# karmanDB_amp.net
KiCad netlist of a schematic drawn in Altium Designer
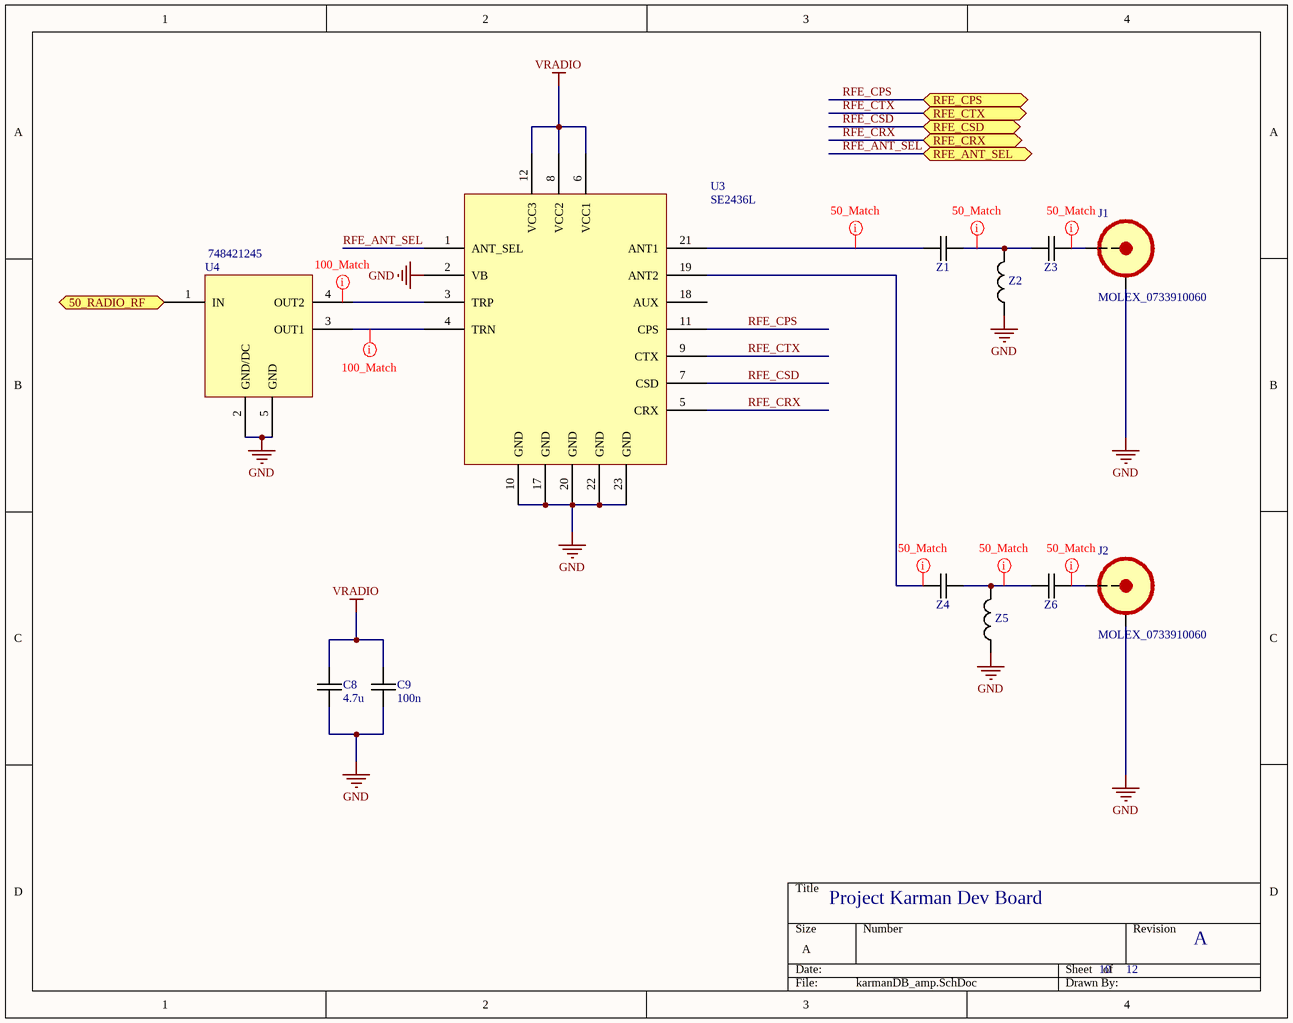
[diagram p0: karmanDB_amp.SchDoc]

(export (version "E")
  (design (tool "Eeschema 10.0.6"))
  (components
    (comp (ref "C8")
      (value "4.7u")
      (footprint "MURATA_GRM_0603")
      (description "CAP CER 4.7UF 16V 20% X5R 0603")
      (fields
        (field (name "MANUFACTURER") "Murata Electronics North America")
        (field (name "MANUFACTURER PART NUMBER") "GRM188R61C475MAAJD")
      )
      (libsource (lib "project_symbols") (part "CAP_MURATA_GRM188R61C475MAAJD"))
    )
    (comp (ref "C9")
      (value "100n")
      (footprint "MURATA_GRM_0603")
      (description "CAP CER 0.1UF 16V 10% X7R 0603")
      (fields
        (field (name "MANUFACTURER") "Murata Electronics North America")
        (field (name "MANUFACTURER PART NUMBER") "GRM188R71C104KA01D")
      )
      (libsource (lib "project_symbols") (part "CAP_MURATA_GRM188R71C104KA01D"))
    )
    (comp (ref "J1")
      (value "MOLEX_0733910060")
      (footprint "MOLEX_0733910060")
      (description "CONN SMA JACK STR 50 OHM PCB")
      (fields
        (field (name "MANUFACTURER") "Molex Inc")
        (field (name "MANUFACTURER PART NUMBER") "0733910060")
      )
      (libsource (lib "project_symbols") (part "MOLEX_0733910060"))
    )
    (comp (ref "J2")
      (value "MOLEX_0733910060")
      (footprint "MOLEX_0733910060")
      (description "CONN SMA JACK STR 50 OHM PCB")
      (fields
        (field (name "MANUFACTURER") "Molex Inc")
        (field (name "MANUFACTURER PART NUMBER") "0733910060")
      )
      (libsource (lib "project_symbols") (part "MOLEX_0733910060"))
    )
    (comp (ref "U3")
      (value "SE2436L")
      (footprint "9 SE2436L")
      (description "ZIGBEE FRONT END MODULE")
      (fields (field (name "MANUFACTURER") "Skyworks Solutions Inc."))
      (libsource (lib "karman_pcb") (part "SE2436L"))
    )
    (comp (ref "U4")
      (value "748421245")
      (footprint "748421245")
      (description "BALUN EMBER351 & 357 0805 SMD")
      (fields (field (name "MANUFACTURER") "Wurth Electronics Inc"))
      (libsource (lib "karman_pcb") (part "748421245"))
    )
    (comp (ref "Z1")
      (value "CAP_GENERIC_0402")
      (footprint "MURATA_GRM_0402")
      (description "Generic Capacitor 0402 Package")
      (libsource (lib "project_symbols") (part "CAP_GENERIC_0402"))
    )
    (comp (ref "Z2")
      (value "IND_GENERIC_0402")
      (footprint "PANASONIC_ELJRF")
      (description "Generic Inductor 0402 Package")
      (libsource (lib "project_symbols") (part "IND_GENERIC_0402"))
    )
    (comp (ref "Z3")
      (value "CAP_GENERIC_0402")
      (footprint "MURATA_GRM_0402")
      (description "Generic Capacitor 0402 Package")
      (libsource (lib "project_symbols") (part "CAP_GENERIC_0402"))
    )
    (comp (ref "Z4")
      (value "CAP_GENERIC_0402")
      (footprint "MURATA_GRM_0402")
      (description "Generic Capacitor 0402 Package")
      (libsource (lib "project_symbols") (part "CAP_GENERIC_0402"))
    )
    (comp (ref "Z5")
      (value "IND_GENERIC_0402")
      (footprint "PANASONIC_ELJRF")
      (description "Generic Inductor 0402 Package")
      (libsource (lib "project_symbols") (part "IND_GENERIC_0402"))
    )
    (comp (ref "Z6")
      (value "CAP_GENERIC_0402")
      (footprint "MURATA_GRM_0402")
      (description "Generic Capacitor 0402 Package")
      (libsource (lib "project_symbols") (part "CAP_GENERIC_0402"))
    )
  )
  (nets
    (net (code "1") (name "/50_RADIO_RF") (class "Default")
      (node (ref "U4") (pin "1") (pinfunction "IN_1") (pintype "passive"))
    )
    (net (code "2") (name "/RFE_ANT_SEL") (class "Default")
      (node (ref "U3") (pin "1") (pinfunction "ANT_SEL_1") (pintype "passive"))
    )
    (net (code "3") (name "/RFE_CPS") (class "Default")
      (node (ref "U3") (pin "11") (pinfunction "CPS_11") (pintype "passive"))
    )
    (net (code "4") (name "/RFE_CRX") (class "Default")
      (node (ref "U3") (pin "5") (pinfunction "CRX_5") (pintype "passive"))
    )
    (net (code "5") (name "/RFE_CSD") (class "Default")
      (node (ref "U3") (pin "7") (pinfunction "CSD_7") (pintype "passive"))
    )
    (net (code "6") (name "/RFE_CTX") (class "Default")
      (node (ref "U3") (pin "9") (pinfunction "CTX_9") (pintype "passive"))
    )
    (net (code "7") (name "GND") (class "Default")
      (node (ref "C8") (pin "2") (pintype "passive"))
      (node (ref "C9") (pin "2") (pintype "passive"))
      (node (ref "J1") (pin "SHIELD") (pintype "passive"))
      (node (ref "J2") (pin "SHIELD") (pintype "passive"))
      (node (ref "U3") (pin "10") (pinfunction "GND_10") (pintype "passive"))
      (node (ref "U3") (pin "17") (pinfunction "GND_17") (pintype "passive"))
      (node (ref "U3") (pin "2") (pinfunction "VB_2") (pintype "passive"))
      (node (ref "U3") (pin "20") (pinfunction "GND_20") (pintype "passive"))
      (node (ref "U3") (pin "22") (pinfunction "GND_22") (pintype "passive"))
      (node (ref "U3") (pin "23") (pinfunction "GND_23") (pintype "passive"))
      (node (ref "U4") (pin "2") (pinfunction "GND/DC_2") (pintype "passive"))
      (node (ref "U4") (pin "5") (pinfunction "GND_5") (pintype "passive"))
      (node (ref "Z2") (pin "1") (pinfunction "1_1") (pintype "passive"))
      (node (ref "Z5") (pin "1") (pinfunction "1_1") (pintype "passive"))
    )
    (net (code "8") (name "Net-(J1-PadPIN)") (class "Default")
      (node (ref "J1") (pin "PIN") (pintype "passive"))
      (node (ref "Z3") (pin "2") (pintype "passive"))
    )
    (net (code "9") (name "Net-(J2-PadPIN)") (class "Default")
      (node (ref "J2") (pin "PIN") (pintype "passive"))
      (node (ref "Z6") (pin "2") (pintype "passive"))
    )
    (net (code "10") (name "Net-(U3-ANT1)") (class "Default")
      (node (ref "U3") (pin "21") (pinfunction "ANT1_21") (pintype "passive"))
      (node (ref "Z1") (pin "1") (pintype "passive"))
    )
    (net (code "11") (name "Net-(U3-ANT2)") (class "Default")
      (node (ref "U3") (pin "19") (pinfunction "ANT2_19") (pintype "passive"))
      (node (ref "Z4") (pin "1") (pintype "passive"))
    )
    (net (code "12") (name "Net-(U3-TRN)") (class "Default")
      (node (ref "U3") (pin "4") (pinfunction "TRN_4") (pintype "passive"))
      (node (ref "U4") (pin "3") (pinfunction "OUT1_3") (pintype "passive"))
    )
    (net (code "13") (name "Net-(U3-TRP)") (class "Default")
      (node (ref "U3") (pin "3") (pinfunction "TRP_3") (pintype "passive"))
      (node (ref "U4") (pin "4") (pinfunction "OUT2_4") (pintype "passive"))
    )
    (net (code "14") (name "Net-(Z1-Pad2)") (class "Default")
      (node (ref "Z1") (pin "2") (pintype "passive"))
      (node (ref "Z2") (pin "2") (pinfunction "2_2") (pintype "passive"))
      (node (ref "Z3") (pin "1") (pintype "passive"))
    )
    (net (code "15") (name "Net-(Z4-Pad2)") (class "Default")
      (node (ref "Z4") (pin "2") (pintype "passive"))
      (node (ref "Z5") (pin "2") (pinfunction "2_2") (pintype "passive"))
      (node (ref "Z6") (pin "1") (pintype "passive"))
    )
    (net (code "16") (name "VRADIO") (class "Default")
      (node (ref "C8") (pin "1") (pintype "passive"))
      (node (ref "C9") (pin "1") (pintype "passive"))
      (node (ref "U3") (pin "12") (pinfunction "VCC3_12") (pintype "passive"))
      (node (ref "U3") (pin "6") (pinfunction "VCC1_6") (pintype "passive"))
      (node (ref "U3") (pin "8") (pinfunction "VCC2_8") (pintype "passive"))
    )
    (net (code "17") (name "unconnected-(U3-AUX-Pad18)") (class "Default")
      (node (ref "U3") (pin "18") (pinfunction "AUX_18") (pintype "passive"))
    )
  )
)
